# GSM.net
KiCad netlist of a schematic drawn in Altium Designer
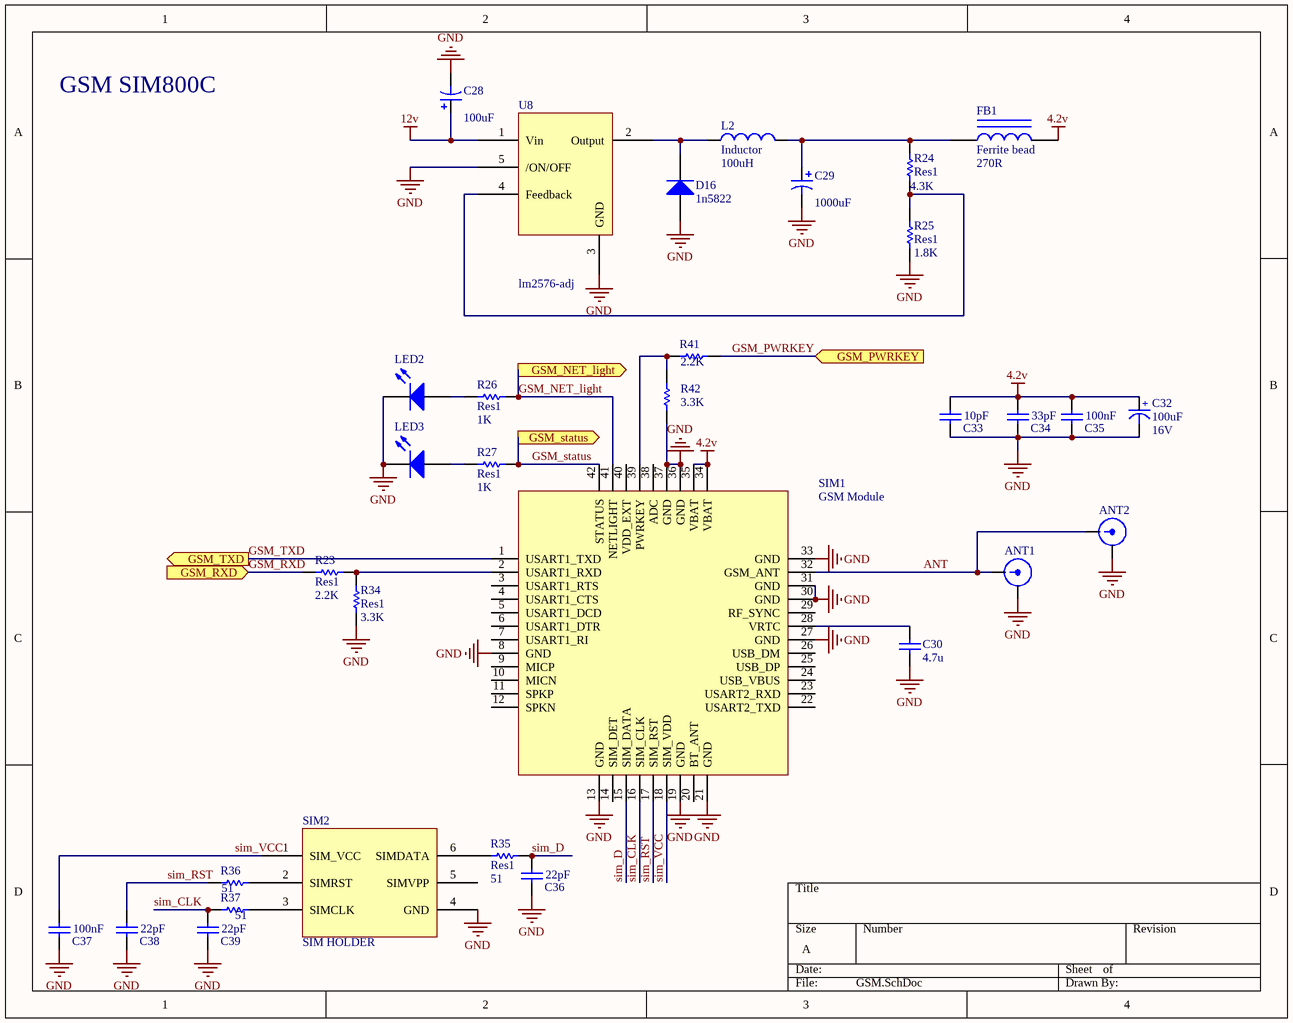
[diagram p0: GSM.SchDoc]

(export (version "E")
  (design (tool "Eeschema 10.0.6"))
  (components
    (comp (ref "ANT1")
      (value "Antenna")
      (footprint "SMA")
      (fields (field (name "DESIGNER") "Ali Hafizi"))
      (libsource (lib "Altium (2)") (part "ANT SMA"))
    )
    (comp (ref "ANT2")
      (value "Antenna")
      (footprint "UFL ant")
      (fields (field (name "DESIGNER") "Ali Hafizi"))
      (libsource (lib "Altium (2)") (part "ANT SMA"))
    )
    (comp (ref "C28")
      (value "100uF")
      (footprint "Cap SMD 100UF 35~50v")
      (description "Polarized Capacitor (Radial)")
      (fields (field (name "PUBLISHER") "Altium Limited"))
      (libsource (lib "Miscellaneous Devices") (part "Cap Pol1"))
    )
    (comp (ref "C29")
      (value "1000uF")
      (footprint "CAP SMD 1000UF 16V")
      (description "Polarized Capacitor (Radial)")
      (fields (field (name "PUBLISHER") "Altium Limited"))
      (libsource (lib "Miscellaneous Devices") (part "Cap Pol1"))
    )
    (comp (ref "C30")
      (value "4.7u")
      (footprint "CAP 1206 (3216X15L)")
      (description "CAP-100Nf")
      (fields (field (name "Comment") "Cap"))
      (libsource (lib "Altium library (www.AVRelec.com)") (part "Cap ceramic"))
    )
    (comp (ref "C32")
      (value "100uF")
      (footprint "cap 01")
      (description "Polar Capacitor")
      (fields (field (name "VOLTAGE") "16V") (field (name "DESIGNER") "Saeid Jorablo"))
      (libsource (lib "My Library") (part "Cap-Polar"))
    )
    (comp (ref "C33")
      (value "10pF")
      (footprint "CAP 1206 (3216X15L)")
      (description "CAP-100Nf")
      (fields (field (name "Comment") "Cap"))
      (libsource (lib "Altium library (www.AVRelec.com)") (part "Cap ceramic"))
    )
    (comp (ref "C34")
      (value "33pF")
      (footprint "CAP 1206 (3216X15L)")
      (description "CAP-100Nf")
      (fields (field (name "Comment") "Cap"))
      (libsource (lib "Altium library (www.AVRelec.com)") (part "Cap ceramic"))
    )
    (comp (ref "C35")
      (value "100nF")
      (footprint "CAP 1206 (3216X15L)")
      (description "CAP-100Nf")
      (fields (field (name "Comment") "Cap"))
      (libsource (lib "Altium library (www.AVRelec.com)") (part "Cap ceramic"))
    )
    (comp (ref "C36")
      (value "22pF")
      (footprint "CAP 1206 (3216X15L)")
      (description "CAP-100Nf")
      (fields (field (name "Comment") "Cap"))
      (libsource (lib "Altium library (www.AVRelec.com)") (part "Cap ceramic"))
    )
    (comp (ref "C37")
      (value "100nF")
      (footprint "CAP 1206 (3216X15L)")
      (description "CAP-100Nf")
      (fields (field (name "Comment") "Cap"))
      (libsource (lib "Altium library (www.AVRelec.com)") (part "Cap ceramic"))
    )
    (comp (ref "C38")
      (value "22pF")
      (footprint "CAP 1206 (3216X15L)")
      (description "CAP-100Nf")
      (fields (field (name "Comment") "Cap"))
      (libsource (lib "Altium library (www.AVRelec.com)") (part "Cap ceramic"))
    )
    (comp (ref "C39")
      (value "22pF")
      (footprint "CAP 1206 (3216X15L)")
      (description "CAP-100Nf")
      (fields (field (name "Comment") "Cap"))
      (libsource (lib "Altium library (www.AVRelec.com)") (part "Cap ceramic"))
    )
    (comp (ref "D16")
      (value "1n5822")
      (footprint "SMA DIODE 2")
      (description "1 Amp General Purpose Rectifier")
      (fields (field (name "PUBLISHER") "Altium Limited"))
      (libsource (lib "Miscellaneous Devices") (part "Diode 1N4007"))
    )
    (comp (ref "FB1")
      (value "Ferrite bead")
      (footprint "FB1206")
      (description "Magnetic-Core Inductor")
      (fields (field (name "ALTIUM_VALUE") "270R") (field (name "PUBLISHER") "Altium Limited"))
      (libsource (lib "Miscellaneous Devices") (part "Inductor Iron"))
    )
    (comp (ref "L2")
      (value "Inductor")
      (footprint "inductor")
      (fields (field (name "ALTIUM_VALUE") "100uH") (field (name "PUBLISHER") "Altium Limited"))
      (libsource (lib "Miscellaneous Devices") (part "Inductor"))
    )
    (comp (ref "LED2")
      (value "LED")
      (footprint "LED 1206")
      (description "Typical INFRARED GaAs LED")
      (fields (field (name "PUBLISHER") "Altium Limited"))
      (libsource (lib "Altium library (www.AVRelec.com)") (part "LED"))
    )
    (comp (ref "LED3")
      (value "LED")
      (footprint "LED 1206")
      (description "Typical INFRARED GaAs LED")
      (fields (field (name "PUBLISHER") "Altium Limited"))
      (libsource (lib "Altium library (www.AVRelec.com)") (part "LED"))
    )
    (comp (ref "R23")
      (value "Res1")
      (footprint "RES 1206 (3216X08L)")
      (description "Resistor")
      (fields (field (name "ALTIUM_VALUE") "2.2K") (field (name "PUBLISHER") "Altium Limited"))
      (libsource (lib "Miscellaneous Devices") (part "Res1"))
    )
    (comp (ref "R24")
      (value "Res1")
      (footprint "RES 1206 (3216X08L)")
      (description "Resistor")
      (fields (field (name "ALTIUM_VALUE") "4.3K") (field (name "PUBLISHER") "Altium Limited"))
      (libsource (lib "Miscellaneous Devices") (part "Res1"))
    )
    (comp (ref "R25")
      (value "Res1")
      (footprint "RES 1206 (3216X08L)")
      (description "Resistor")
      (fields (field (name "ALTIUM_VALUE") "1.8K") (field (name "PUBLISHER") "Altium Limited"))
      (libsource (lib "Miscellaneous Devices") (part "Res1"))
    )
    (comp (ref "R26")
      (value "Res1")
      (footprint "RES 1206 (3216X08L)")
      (description "Resistor")
      (fields (field (name "ALTIUM_VALUE") "1K") (field (name "PUBLISHER") "Altium Limited"))
      (libsource (lib "Miscellaneous Devices") (part "Res1"))
    )
    (comp (ref "R27")
      (value "Res1")
      (footprint "RES 1206 (3216X08L)")
      (description "Resistor")
      (fields (field (name "ALTIUM_VALUE") "1K") (field (name "PUBLISHER") "Altium Limited"))
      (libsource (lib "Miscellaneous Devices") (part "Res1"))
    )
    (comp (ref "R34")
      (value "Res1")
      (footprint "RES 1206 (3216X08L)")
      (description "Resistor")
      (fields (field (name "ALTIUM_VALUE") "3.3K") (field (name "PUBLISHER") "Altium Limited"))
      (libsource (lib "Miscellaneous Devices") (part "Res1"))
    )
    (comp (ref "R35")
      (value "Res1")
      (footprint "RES 1206 (3216X08L)")
      (description "Resistor")
      (fields (field (name "ALTIUM_VALUE") "51") (field (name "PUBLISHER") "Altium Limited"))
      (libsource (lib "Miscellaneous Devices") (part "Res1"))
    )
    (comp (ref "R36")
      (value "51")
      (footprint "RES 1206 (3216X08L)")
      (description "Resistor")
      (fields (field (name "Comment") "Res1") (field (name "PUBLISHER") "Altium Limited"))
      (libsource (lib "Miscellaneous Devices") (part "Res1"))
    )
    (comp (ref "R37")
      (value "51")
      (footprint "RES 1206 (3216X08L)")
      (description "Resistor")
      (fields (field (name "Comment") "Res1") (field (name "PUBLISHER") "Altium Limited"))
      (libsource (lib "Miscellaneous Devices") (part "Res1"))
    )
    (comp (ref "R41")
      (value "2.2K")
      (footprint "RES 1206 (3216X08L)")
      (description "Resistor")
      (fields (field (name "Comment") "Res1") (field (name "PUBLISHER") "Altium Limited"))
      (libsource (lib "Miscellaneous Devices") (part "Res1"))
    )
    (comp (ref "R42")
      (value "3.3K")
      (footprint "RES 1206 (3216X08L)")
      (description "Resistor")
      (fields (field (name "Comment") "Res1") (field (name "PUBLISHER") "Altium Limited"))
      (libsource (lib "Miscellaneous Devices") (part "Res1"))
    )
    (comp (ref "SIM1")
      (value "GSM Module")
      (footprint "SIM800C")
      (fields (field (name "DESIGNER") "Ali Hafizi"))
      (libsource (lib "Altium (2)") (part "SIM800C"))
    )
    (comp (ref "SIM2")
      (value "SIM HOLDER")
      (footprint "simcard_holder")
      (libsource (lib "Altium (2)") (part "SIM HOLDER"))
    )
    (comp (ref "U8") (value "lm2576-adj") (footprint "2596") (libsource (lib "No.2") (part "lm2596")))
  )
  (nets
    (net (code "1") (name "/ANT") (class "Default")
      (node (ref "ANT1") (pin "1") (pinfunction "1_1") (pintype "passive"))
      (node (ref "ANT2") (pin "1") (pinfunction "1_1") (pintype "passive"))
      (node (ref "SIM1") (pin "32") (pinfunction "GSM_ANT_32") (pintype "passive"))
    )
    (net (code "2") (name "/GSM_NET_light") (class "Default")
      (node (ref "R26") (pin "1") (pinfunction "1_1") (pintype "passive"))
      (node (ref "SIM1") (pin "41") (pinfunction "NETLIGHT_41") (pintype "passive"))
    )
    (net (code "3") (name "/GSM_PWRKEY") (class "Default")
      (node (ref "R41") (pin "1") (pinfunction "1_1") (pintype "passive"))
    )
    (net (code "4") (name "/GSM_RXD") (class "Default")
      (node (ref "R23") (pin "2") (pinfunction "2_2") (pintype "passive"))
    )
    (net (code "5") (name "/GSM_TXD") (class "Default")
      (node (ref "SIM1") (pin "1") (pinfunction "USART1_TXD_1") (pintype "passive"))
    )
    (net (code "6") (name "/GSM_status") (class "Default")
      (node (ref "R27") (pin "1") (pinfunction "1_1") (pintype "passive"))
      (node (ref "SIM1") (pin "42") (pinfunction "STATUS_42") (pintype "passive"))
    )
    (net (code "7") (name "/sim_CLK") (class "Default")
      (node (ref "C39") (pin "2") (pinfunction "2_2") (pintype "passive"))
      (node (ref "R37") (pin "1") (pinfunction "1_1") (pintype "passive"))
      (node (ref "SIM1") (pin "16") (pinfunction "SIM_CLK_16") (pintype "passive"))
    )
    (net (code "8") (name "/sim_D") (class "Default")
      (node (ref "C36") (pin "2") (pinfunction "2_2") (pintype "passive"))
      (node (ref "R35") (pin "2") (pinfunction "2_2") (pintype "passive"))
      (node (ref "SIM1") (pin "15") (pinfunction "SIM_DATA_15") (pintype "passive"))
    )
    (net (code "9") (name "/sim_RST") (class "Default")
      (node (ref "C38") (pin "2") (pinfunction "2_2") (pintype "passive"))
      (node (ref "R36") (pin "1") (pinfunction "1_1") (pintype "passive"))
      (node (ref "SIM1") (pin "17") (pinfunction "SIM_RST_17") (pintype "passive"))
    )
    (net (code "10") (name "/sim_VCC") (class "Default")
      (node (ref "C37") (pin "2") (pinfunction "2_2") (pintype "passive"))
      (node (ref "SIM1") (pin "18") (pinfunction "SIM_VDD_18") (pintype "passive"))
      (node (ref "SIM2") (pin "1") (pinfunction "SIM_VCC_1") (pintype "passive"))
    )
    (net (code "11") (name "4.2v") (class "Default")
      (node (ref "C32") (pin "1") (pinfunction "+_1") (pintype "passive"))
      (node (ref "C33") (pin "2") (pinfunction "2_2") (pintype "passive"))
      (node (ref "C34") (pin "2") (pinfunction "2_2") (pintype "passive"))
      (node (ref "C35") (pin "2") (pinfunction "2_2") (pintype "passive"))
      (node (ref "FB1") (pin "2") (pinfunction "2_2") (pintype "passive"))
      (node (ref "SIM1") (pin "34") (pinfunction "VBAT_34") (pintype "passive"))
      (node (ref "SIM1") (pin "35") (pinfunction "VBAT_35") (pintype "passive"))
    )
    (net (code "12") (name "12v") (class "Default")
      (node (ref "C28") (pin "1") (pinfunction "1_1") (pintype "passive"))
      (node (ref "U8") (pin "1") (pinfunction "Vin_1") (pintype "power_in"))
    )
    (net (code "13") (name "GND") (class "Default")
      (node (ref "ANT1") (pin "2") (pinfunction "2_2") (pintype "passive"))
      (node (ref "ANT2") (pin "2") (pinfunction "2_2") (pintype "passive"))
      (node (ref "C28") (pin "2") (pinfunction "2_2") (pintype "passive"))
      (node (ref "C29") (pin "2") (pinfunction "2_2") (pintype "passive"))
      (node (ref "C30") (pin "1") (pinfunction "1_1") (pintype "passive"))
      (node (ref "C32") (pin "2") (pinfunction "-_2") (pintype "passive"))
      (node (ref "C33") (pin "1") (pinfunction "1_1") (pintype "passive"))
      (node (ref "C34") (pin "1") (pinfunction "1_1") (pintype "passive"))
      (node (ref "C35") (pin "1") (pinfunction "1_1") (pintype "passive"))
      (node (ref "C36") (pin "1") (pinfunction "1_1") (pintype "passive"))
      (node (ref "C37") (pin "1") (pinfunction "1_1") (pintype "passive"))
      (node (ref "C38") (pin "1") (pinfunction "1_1") (pintype "passive"))
      (node (ref "C39") (pin "1") (pinfunction "1_1") (pintype "passive"))
      (node (ref "D16") (pin "1") (pinfunction "A_1") (pintype "passive"))
      (node (ref "LED2") (pin "K") (pinfunction "K_K") (pintype "passive"))
      (node (ref "LED3") (pin "K") (pinfunction "K_K") (pintype "passive"))
      (node (ref "R25") (pin "1") (pinfunction "1_1") (pintype "passive"))
      (node (ref "R34") (pin "2") (pinfunction "2_2") (pintype "passive"))
      (node (ref "R42") (pin "1") (pinfunction "1_1") (pintype "passive"))
      (node (ref "SIM1") (pin "13") (pinfunction "GND_13") (pintype "passive"))
      (node (ref "SIM1") (pin "19") (pinfunction "GND_19") (pintype "passive"))
      (node (ref "SIM1") (pin "21") (pinfunction "GND_21") (pintype "passive"))
      (node (ref "SIM1") (pin "27") (pinfunction "GND_27") (pintype "passive"))
      (node (ref "SIM1") (pin "30") (pinfunction "GND_30") (pintype "passive"))
      (node (ref "SIM1") (pin "31") (pinfunction "GND_31") (pintype "passive"))
      (node (ref "SIM1") (pin "33") (pinfunction "GND_33") (pintype "passive"))
      (node (ref "SIM1") (pin "36") (pinfunction "GND_36") (pintype "passive"))
      (node (ref "SIM1") (pin "37") (pinfunction "GND_37") (pintype "passive"))
      (node (ref "SIM1") (pin "8") (pinfunction "GND_8") (pintype "passive"))
      (node (ref "SIM2") (pin "4") (pinfunction "GND_4") (pintype "passive"))
      (node (ref "U8") (pin "3") (pinfunction "GND_3") (pintype "power_in"))
      (node (ref "U8") (pin "5") (pinfunction "/ON/OFF_5") (pintype "power_in"))
    )
    (net (code "14") (name "Net-(C29-Pad1)") (class "Default")
      (node (ref "C29") (pin "1") (pinfunction "1_1") (pintype "passive"))
      (node (ref "FB1") (pin "1") (pinfunction "1_1") (pintype "passive"))
      (node (ref "L2") (pin "2") (pinfunction "2_2") (pintype "passive"))
      (node (ref "R24") (pin "2") (pinfunction "2_2") (pintype "passive"))
    )
    (net (code "15") (name "Net-(D16-K)") (class "Default")
      (node (ref "D16") (pin "2") (pinfunction "K_2") (pintype "passive"))
      (node (ref "L2") (pin "1") (pinfunction "1_1") (pintype "passive"))
      (node (ref "U8") (pin "2") (pinfunction "Output_2") (pintype "power_in"))
    )
    (net (code "16") (name "Net-(LED2-PadA)") (class "Default")
      (node (ref "LED2") (pin "A") (pinfunction "A_A") (pintype "passive"))
      (node (ref "R26") (pin "2") (pinfunction "2_2") (pintype "passive"))
    )
    (net (code "17") (name "Net-(LED3-PadA)") (class "Default")
      (node (ref "LED3") (pin "A") (pinfunction "A_A") (pintype "passive"))
      (node (ref "R27") (pin "2") (pinfunction "2_2") (pintype "passive"))
    )
    (net (code "18") (name "Net-(SIM1-PWRKEY)") (class "Default")
      (node (ref "R41") (pin "2") (pinfunction "2_2") (pintype "passive"))
      (node (ref "R42") (pin "2") (pinfunction "2_2") (pintype "passive"))
      (node (ref "SIM1") (pin "39") (pinfunction "PWRKEY_39") (pintype "passive"))
    )
    (net (code "19") (name "Net-(SIM1-USART1_RXD)") (class "Default")
      (node (ref "R23") (pin "1") (pinfunction "1_1") (pintype "passive"))
      (node (ref "R34") (pin "1") (pinfunction "1_1") (pintype "passive"))
      (node (ref "SIM1") (pin "2") (pinfunction "USART1_RXD_2") (pintype "passive"))
    )
    (net (code "20") (name "Net-(SIM1-VRTC)") (class "Default")
      (node (ref "C30") (pin "2") (pinfunction "2_2") (pintype "passive"))
      (node (ref "SIM1") (pin "28") (pinfunction "VRTC_28") (pintype "passive"))
    )
    (net (code "21") (name "Net-(SIM2-SIMCLK)") (class "Default")
      (node (ref "R37") (pin "2") (pinfunction "2_2") (pintype "passive"))
      (node (ref "SIM2") (pin "3") (pinfunction "SIMCLK_3") (pintype "passive"))
    )
    (net (code "22") (name "Net-(SIM2-SIMDATA)") (class "Default")
      (node (ref "R35") (pin "1") (pinfunction "1_1") (pintype "passive"))
      (node (ref "SIM2") (pin "6") (pinfunction "SIMDATA_6") (pintype "passive"))
    )
    (net (code "23") (name "Net-(SIM2-SIMRST)") (class "Default")
      (node (ref "R36") (pin "2") (pinfunction "2_2") (pintype "passive"))
      (node (ref "SIM2") (pin "2") (pinfunction "SIMRST_2") (pintype "passive"))
    )
    (net (code "24") (name "Net-(U8-Feedback)") (class "Default")
      (node (ref "R24") (pin "1") (pinfunction "1_1") (pintype "passive"))
      (node (ref "R25") (pin "2") (pinfunction "2_2") (pintype "passive"))
      (node (ref "U8") (pin "4") (pinfunction "Feedback_4") (pintype "power_in"))
    )
    (net (code "25") (name "unconnected-(SIM1-ADC-Pad38)") (class "Default")
      (node (ref "SIM1") (pin "38") (pinfunction "ADC_38") (pintype "passive"))
    )
    (net (code "26") (name "unconnected-(SIM1-BT_ANT-Pad20)") (class "Default")
      (node (ref "SIM1") (pin "20") (pinfunction "BT_ANT_20") (pintype "passive"))
    )
    (net (code "27") (name "unconnected-(SIM1-MICN-Pad10)") (class "Default")
      (node (ref "SIM1") (pin "10") (pinfunction "MICN_10") (pintype "passive"))
    )
    (net (code "28") (name "unconnected-(SIM1-MICP-Pad9)") (class "Default")
      (node (ref "SIM1") (pin "9") (pinfunction "MICP_9") (pintype "passive"))
    )
    (net (code "29") (name "unconnected-(SIM1-RF_SYNC-Pad29)") (class "Default")
      (node (ref "SIM1") (pin "29") (pinfunction "RF_SYNC_29") (pintype "passive"))
    )
    (net (code "30") (name "unconnected-(SIM1-SIM_DET-Pad14)") (class "Default")
      (node (ref "SIM1") (pin "14") (pinfunction "SIM_DET_14") (pintype "passive"))
    )
    (net (code "31") (name "unconnected-(SIM1-SPKN-Pad12)") (class "Default")
      (node (ref "SIM1") (pin "12") (pinfunction "SPKN_12") (pintype "passive"))
    )
    (net (code "32") (name "unconnected-(SIM1-SPKP-Pad11)") (class "Default")
      (node (ref "SIM1") (pin "11") (pinfunction "SPKP_11") (pintype "passive"))
    )
    (net (code "33") (name "unconnected-(SIM1-USART1_CTS-Pad4)") (class "Default")
      (node (ref "SIM1") (pin "4") (pinfunction "USART1_CTS_4") (pintype "passive"))
    )
    (net (code "34") (name "unconnected-(SIM1-USART1_DCD-Pad5)") (class "Default")
      (node (ref "SIM1") (pin "5") (pinfunction "USART1_DCD_5") (pintype "passive"))
    )
    (net (code "35") (name "unconnected-(SIM1-USART1_DTR-Pad6)") (class "Default")
      (node (ref "SIM1") (pin "6") (pinfunction "USART1_DTR_6") (pintype "passive"))
    )
    (net (code "36") (name "unconnected-(SIM1-USART1_RI-Pad7)") (class "Default")
      (node (ref "SIM1") (pin "7") (pinfunction "USART1_RI_7") (pintype "passive"))
    )
    (net (code "37") (name "unconnected-(SIM1-USART1_RTS-Pad3)") (class "Default")
      (node (ref "SIM1") (pin "3") (pinfunction "USART1_RTS_3") (pintype "passive"))
    )
    (net (code "38") (name "unconnected-(SIM1-USART2_RXD-Pad23)") (class "Default")
      (node (ref "SIM1") (pin "23") (pinfunction "USART2_RXD_23") (pintype "passive"))
    )
    (net (code "39") (name "unconnected-(SIM1-USART2_TXD-Pad22)") (class "Default")
      (node (ref "SIM1") (pin "22") (pinfunction "USART2_TXD_22") (pintype "passive"))
    )
    (net (code "40") (name "unconnected-(SIM1-USB_DM-Pad26)") (class "Default")
      (node (ref "SIM1") (pin "26") (pinfunction "USB_DM_26") (pintype "passive"))
    )
    (net (code "41") (name "unconnected-(SIM1-USB_DP-Pad25)") (class "Default")
      (node (ref "SIM1") (pin "25") (pinfunction "USB_DP_25") (pintype "passive"))
    )
    (net (code "42") (name "unconnected-(SIM1-USB_VBUS-Pad24)") (class "Default")
      (node (ref "SIM1") (pin "24") (pinfunction "USB_VBUS_24") (pintype "passive"))
    )
    (net (code "43") (name "unconnected-(SIM1-VDD_EXT-Pad40)") (class "Default")
      (node (ref "SIM1") (pin "40") (pinfunction "VDD_EXT_40") (pintype "passive"))
    )
    (net (code "44") (name "unconnected-(SIM2-SIMVPP-Pad5)") (class "Default")
      (node (ref "SIM2") (pin "5") (pinfunction "SIMVPP_5") (pintype "passive"))
    )
  )
)
